# ProPrj_51__2025-11-10-23-27-29.net
KiCad netlist of a schematic drawn in EasyEDA Pro
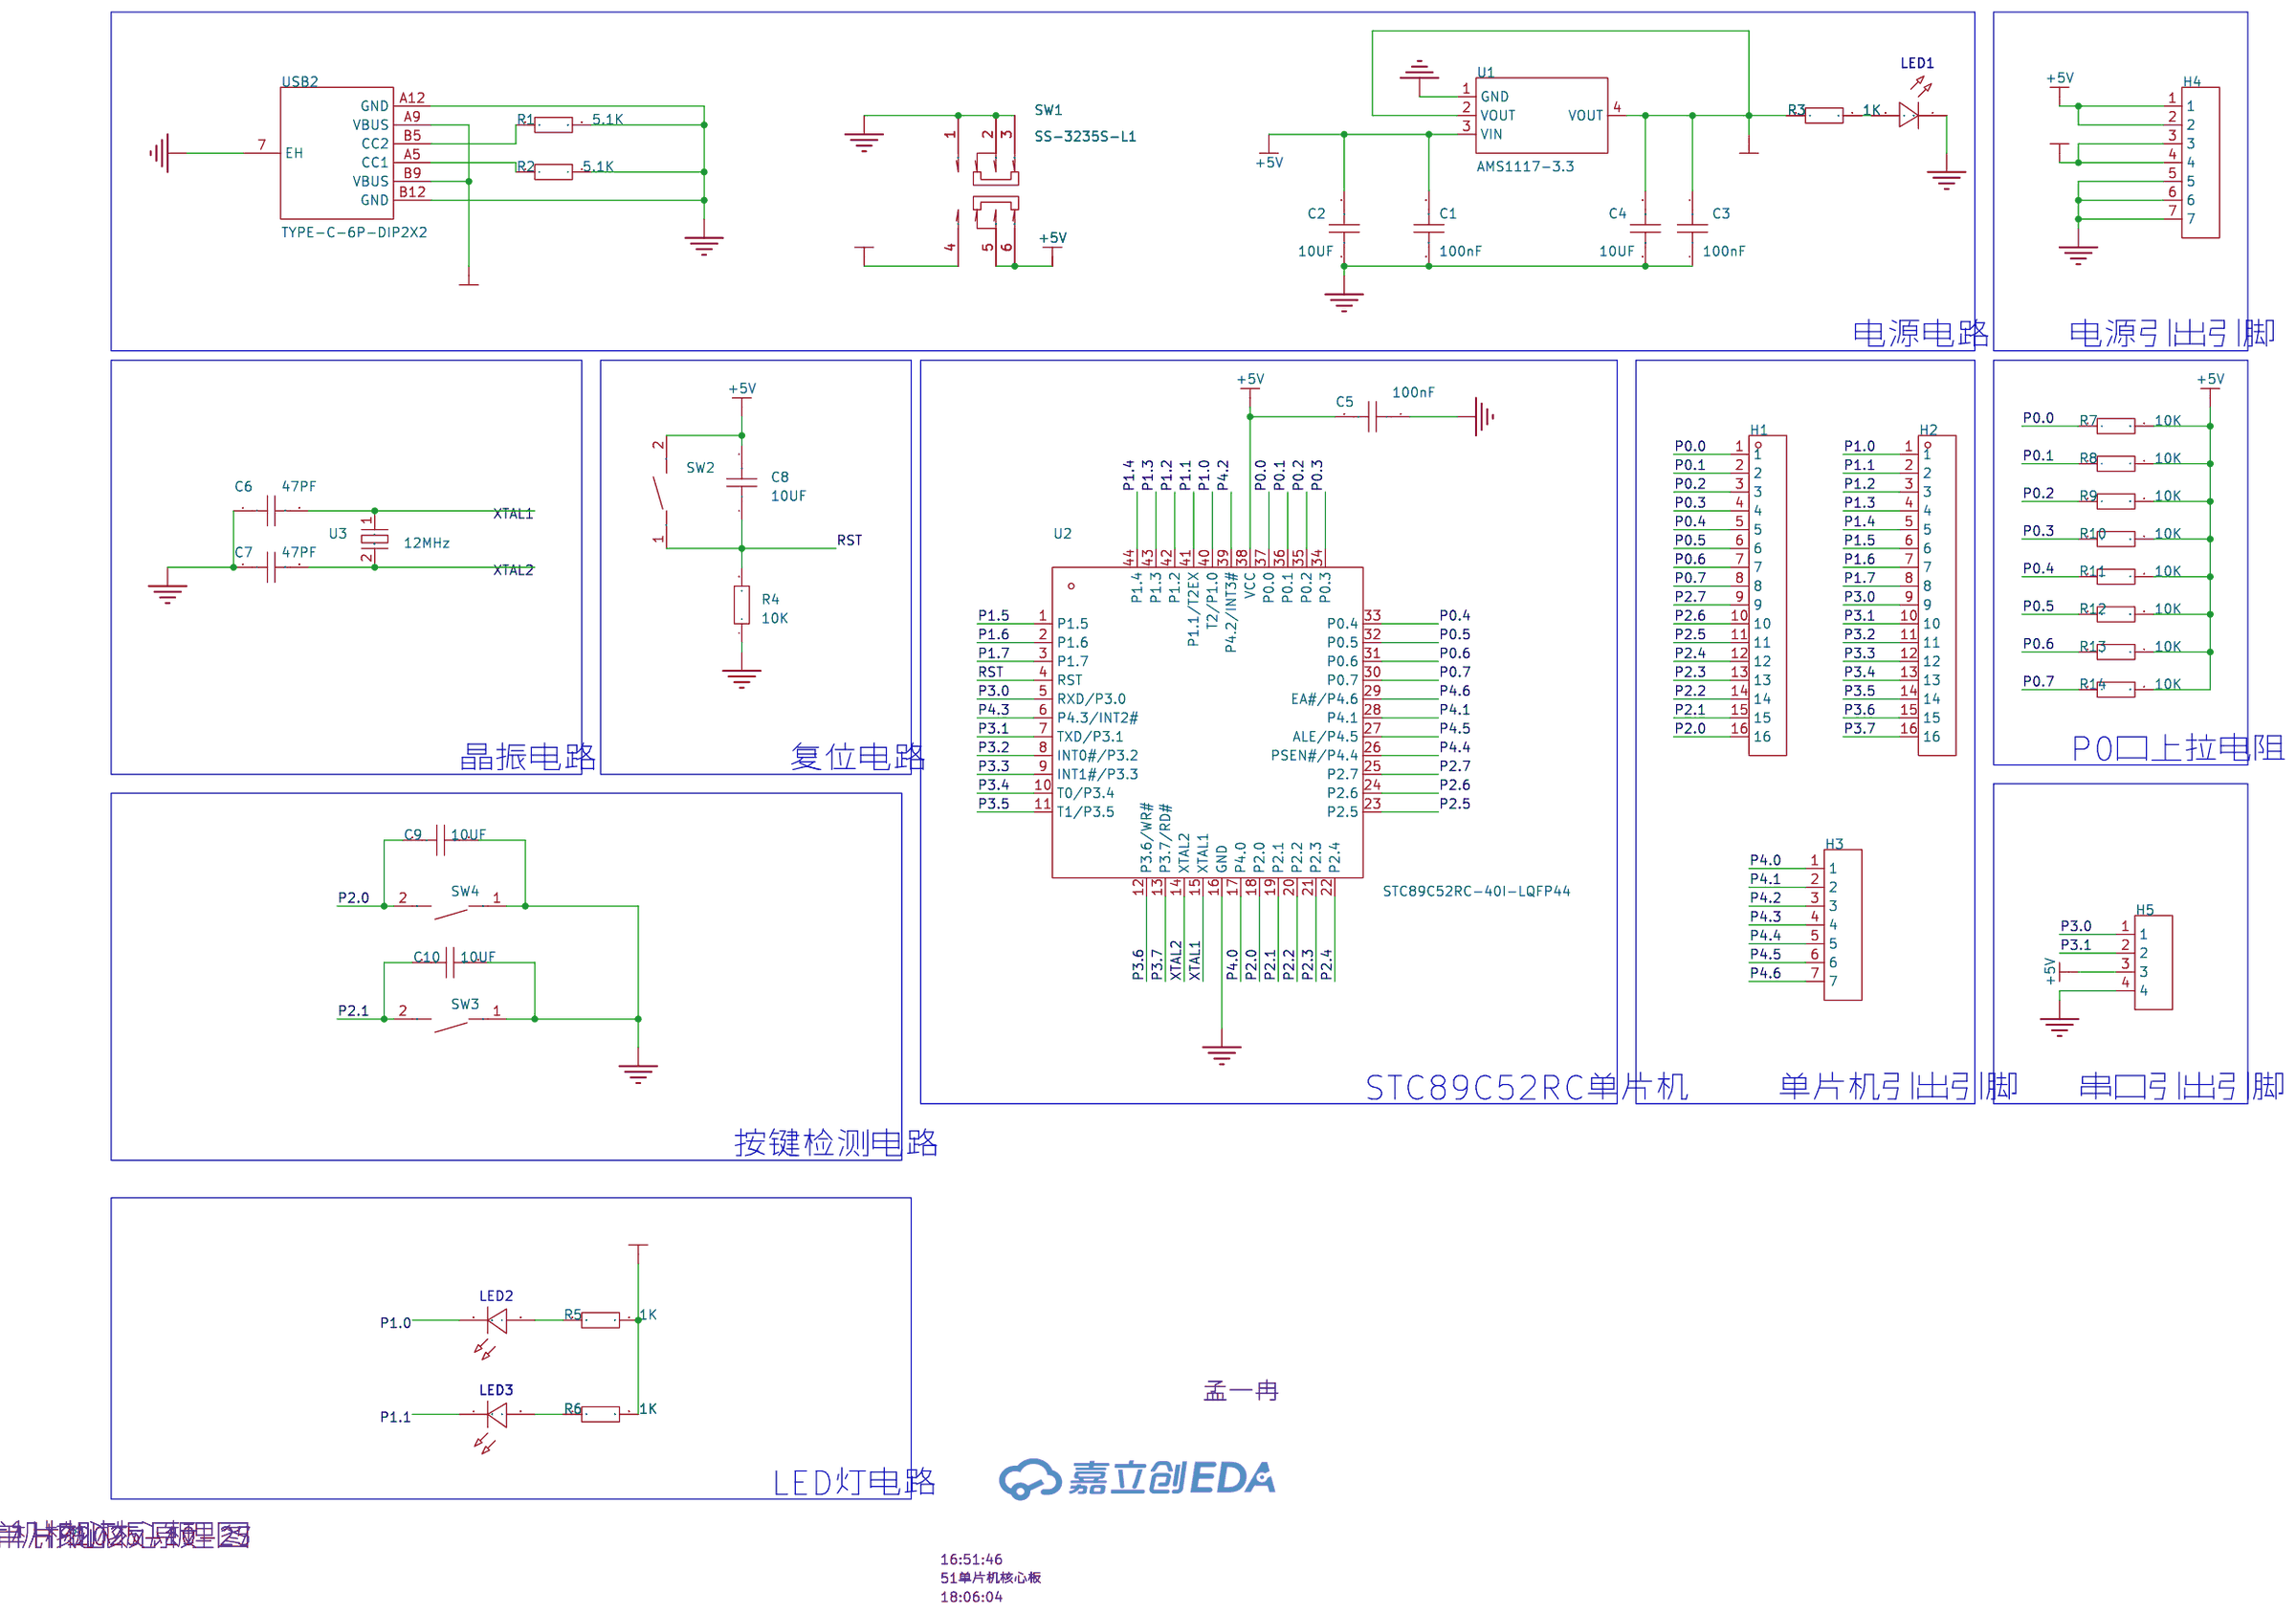
[diagram p0: schematic sheet]

(export (version "E")
  (design (tool "Eeschema 10.0.6"))
  (components
    (comp (ref "C1")
      (value "100nF")
      (footprint "easyedapro:C0805")
      (libsource (lib "easyedapro") (part "Capacitance"))
    )
    (comp (ref "C2")
      (value "10UF")
      (footprint "easyedapro:C0805")
      (libsource (lib "easyedapro") (part "Capacitance"))
    )
    (comp (ref "C3")
      (value "100nF")
      (footprint "easyedapro:C0805")
      (libsource (lib "easyedapro") (part "Capacitance"))
    )
    (comp (ref "C4")
      (value "10UF")
      (footprint "easyedapro:C0805")
      (libsource (lib "easyedapro") (part "Capacitance"))
    )
    (comp (ref "C5")
      (value "100nF")
      (footprint "easyedapro:C0805")
      (libsource (lib "easyedapro") (part "Capacitance"))
    )
    (comp (ref "C6")
      (value "47PF")
      (footprint "easyedapro:C0805")
      (libsource (lib "easyedapro") (part "Capacitance"))
    )
    (comp (ref "C7")
      (value "47PF")
      (footprint "easyedapro:C0805")
      (libsource (lib "easyedapro") (part "Capacitance"))
    )
    (comp (ref "C8")
      (value "10UF")
      (footprint "easyedapro:C0805")
      (libsource (lib "easyedapro") (part "Capacitance"))
    )
    (comp (ref "C9")
      (value "10UF")
      (footprint "easyedapro:C0805")
      (libsource (lib "easyedapro") (part "Capacitance"))
    )
    (comp (ref "C10")
      (value "10UF")
      (footprint "easyedapro:C0805")
      (libsource (lib "easyedapro") (part "Capacitance"))
    )
    (comp (ref "H1")
      (value "~")
      (footprint "easyedapro:HDR-TH_16P-P2.54-V-M")
      (libsource (lib "easyedapro") (part "HDR_2.54-1x16P"))
    )
    (comp (ref "H2")
      (value "~")
      (footprint "easyedapro:HDR-TH_16P-P2.54-V-M")
      (libsource (lib "easyedapro") (part "HDR_2.54-1x16P"))
    )
    (comp (ref "H3")
      (value "~")
      (footprint "easyedapro:HDR-TH_7P-P2.54-V-M")
      (libsource (lib "easyedapro") (part "PZ254V-11-07P"))
    )
    (comp (ref "H4")
      (value "~")
      (footprint "easyedapro:HDR-TH_7P-P2.54-V-M")
      (libsource (lib "easyedapro") (part "PZ254V-11-07P"))
    )
    (comp (ref "H5")
      (value "~")
      (footprint "easyedapro:HDR-TH_4P-P2.54-V-M")
      (libsource (lib "easyedapro") (part "PZ254V-11-04P"))
    )
    (comp (ref "LED1")
      (value "~")
      (footprint "easyedapro:LED_0805")
      (libsource (lib "easyedapro") (part "LED_G"))
    )
    (comp (ref "LED2")
      (value "~")
      (footprint "easyedapro:LED_0805")
      (libsource (lib "easyedapro") (part "LED_G"))
    )
    (comp (ref "LED3")
      (value "~")
      (footprint "easyedapro:LED_0805")
      (libsource (lib "easyedapro") (part "LED_G"))
    )
    (comp (ref "R1") (value "5.1K") (footprint "easyedapro:R0805") (libsource (lib "easyedapro") (part "电阻")))
    (comp (ref "R2") (value "5.1K") (footprint "easyedapro:R0805") (libsource (lib "easyedapro") (part "电阻")))
    (comp (ref "R3") (value "1K") (footprint "easyedapro:R0805") (libsource (lib "easyedapro") (part "电阻")))
    (comp (ref "R4") (value "10K") (footprint "easyedapro:R0805") (libsource (lib "easyedapro") (part "电阻")))
    (comp (ref "R5") (value "1K") (footprint "easyedapro:R0805") (libsource (lib "easyedapro") (part "电阻")))
    (comp (ref "R6") (value "1K") (footprint "easyedapro:R0805") (libsource (lib "easyedapro") (part "电阻")))
    (comp (ref "R7") (value "10K") (footprint "easyedapro:R0805") (libsource (lib "easyedapro") (part "电阻")))
    (comp (ref "R8") (value "10K") (footprint "easyedapro:R0805") (libsource (lib "easyedapro") (part "电阻")))
    (comp (ref "R9") (value "10K") (footprint "easyedapro:R0805") (libsource (lib "easyedapro") (part "电阻")))
    (comp (ref "R10") (value "10K") (footprint "easyedapro:R0805") (libsource (lib "easyedapro") (part "电阻")))
    (comp (ref "R11") (value "10K") (footprint "easyedapro:R0805") (libsource (lib "easyedapro") (part "电阻")))
    (comp (ref "R12") (value "10K") (footprint "easyedapro:R0805") (libsource (lib "easyedapro") (part "电阻")))
    (comp (ref "R13") (value "10K") (footprint "easyedapro:R0805") (libsource (lib "easyedapro") (part "电阻")))
    (comp (ref "R14") (value "10K") (footprint "easyedapro:R0805") (libsource (lib "easyedapro") (part "电阻")))
    (comp (ref "SW1")
      (value "SS-3235S-L1")
      (footprint "easyedapro:SW-SMD_SS-3235S-LX")
      (description "电路结构:双刀双掷;安装方式:卧贴;开关颜色:黑色;额定电流:50mA;额定电压:12V;工作寿命:1万次;")
      (fields (field (name "Manufacturer") "XKB Connection(中国星坤)"))
      (libsource (lib "easyedapro") (part "SS-3235S-L1"))
    )
    (comp (ref "SW2")
      (value "轻触按键3*4*H")
      (footprint "easyedapro:SW-SMD_L4.0-W2.9-LS5.0")
      (libsource (lib "easyedapro") (part "轻触按键3*4*H"))
    )
    (comp (ref "SW3")
      (value "轻触按键3*4*H")
      (footprint "easyedapro:SW-SMD_L4.0-W2.9-LS5.0")
      (libsource (lib "easyedapro") (part "轻触按键3*4*H"))
    )
    (comp (ref "SW4")
      (value "轻触按键3*4*H")
      (footprint "easyedapro:SW-SMD_L4.0-W2.9-LS5.0")
      (libsource (lib "easyedapro") (part "轻触按键3*4*H"))
    )
    (comp (ref "U1")
      (value "AMS1117-3.3")
      (footprint "easyedapro:SOT-223-3_L6.5-W3.4-P2.30-LS7.0-BR")
      (description "输出类型:固定;工作电压:16V;输出电压:3.3V;输出电流:1A;电源纹波抑制比(PSRR):72dB@(120Hz);输出极性:正极;")
      (fields (field (name "Manufacturer") "AMS"))
      (libsource (lib "easyedapro") (part "AMS1117-3.3"))
    )
    (comp (ref "U2")
      (value "STC89C52RC-40I-LQFP44")
      (footprint "easyedapro:LQFP-44_L10.0-W10.0-P0.80-LS12.0-BL")
      (description "CPU内核:51系列;应用领域:-;")
      (fields (field (name "Manufacturer") "STC"))
      (libsource (lib "easyedapro") (part "STC89C52RC-40I_C8707"))
    )
    (comp (ref "U3")
      (value "12MHz")
      (footprint "easyedapro:CRYSTAL-SMD_L11.4-W4.7-LS12.7")
      (description "频率:12MHz;常温频差:±30ppm;外接负载电容:18pF;频率稳定度(全温):±35ppm;")
      (fields
        (field (name "Manufacturer Part") "ABLS-12.000MHZ-B4H-T")
        (field (name "Manufacturer") "ABRACON")
      )
      (libsource (lib "easyedapro") (part "ABLS-12.000MHZ-B4H-T"))
    )
    (comp (ref "USB2")
      (value "TYPE-C-6P-DIP2X2")
      (footprint "easyedapro:TYPE-C-SMD_TYPE-C-6P")
      (libsource (lib "easyedapro") (part "TYPE-C-6P-DIP2X2"))
    )
  )
  (nets
    (net (code "1") (name "+3.3V") (class "Default")
      (node (ref "C3") (pin "2") (pinfunction "2_2") (pintype "input"))
      (node (ref "C4") (pin "2") (pinfunction "2_2") (pintype "input"))
      (node (ref "H4") (pin "3") (pinfunction "3_3") (pintype "unspecified"))
      (node (ref "H4") (pin "4") (pinfunction "4_4") (pintype "unspecified"))
      (node (ref "R3") (pin "1") (pinfunction "1_1") (pintype "input"))
      (node (ref "R5") (pin "2") (pinfunction "2_2") (pintype "input"))
      (node (ref "R6") (pin "2") (pinfunction "2_2") (pintype "input"))
      (node (ref "U1") (pin "2") (pinfunction "VOUT_2") (pintype "unspecified"))
      (node (ref "U1") (pin "4") (pinfunction "VOUT_4") (pintype "unspecified"))
    )
    (net (code "2") (name "+5V") (class "Default")
      (node (ref "C1") (pin "2") (pinfunction "2_2") (pintype "input"))
      (node (ref "C2") (pin "2") (pinfunction "2_2") (pintype "input"))
      (node (ref "C5") (pin "2") (pinfunction "2_2") (pintype "input"))
      (node (ref "C8") (pin "2") (pinfunction "2_2") (pintype "input"))
      (node (ref "H4") (pin "1") (pinfunction "1_1") (pintype "unspecified"))
      (node (ref "H4") (pin "2") (pinfunction "2_2") (pintype "unspecified"))
      (node (ref "H5") (pin "3") (pinfunction "3_3") (pintype "unspecified"))
      (node (ref "R10") (pin "2") (pinfunction "2_2") (pintype "input"))
      (node (ref "R11") (pin "2") (pinfunction "2_2") (pintype "input"))
      (node (ref "R12") (pin "2") (pinfunction "2_2") (pintype "input"))
      (node (ref "R13") (pin "2") (pinfunction "2_2") (pintype "input"))
      (node (ref "R14") (pin "2") (pinfunction "2_2") (pintype "input"))
      (node (ref "R7") (pin "2") (pinfunction "2_2") (pintype "input"))
      (node (ref "R8") (pin "2") (pinfunction "2_2") (pintype "input"))
      (node (ref "R9") (pin "2") (pinfunction "2_2") (pintype "input"))
      (node (ref "SW1") (pin "5") (pinfunction "5_5") (pintype "unspecified"))
      (node (ref "SW1") (pin "6") (pinfunction "6_6") (pintype "unspecified"))
      (node (ref "SW2") (pin "2") (pinfunction "2_2") (pintype "unspecified"))
      (node (ref "U1") (pin "3") (pinfunction "VIN_3") (pintype "unspecified"))
      (node (ref "U2") (pin "38") (pinfunction "VCC_38") (pintype "unspecified"))
    )
    (net (code "3") (name "/P0.0") (class "Default")
      (node (ref "H1") (pin "1") (pinfunction "1_1") (pintype "input"))
      (node (ref "R7") (pin "1") (pinfunction "1_1") (pintype "input"))
      (node (ref "U2") (pin "37") (pinfunction "P0.0_37") (pintype "unspecified"))
    )
    (net (code "4") (name "/P0.1") (class "Default")
      (node (ref "H1") (pin "2") (pinfunction "2_2") (pintype "input"))
      (node (ref "R8") (pin "1") (pinfunction "1_1") (pintype "input"))
      (node (ref "U2") (pin "36") (pinfunction "P0.1_36") (pintype "unspecified"))
    )
    (net (code "5") (name "/P0.2") (class "Default")
      (node (ref "H1") (pin "3") (pinfunction "3_3") (pintype "input"))
      (node (ref "R9") (pin "1") (pinfunction "1_1") (pintype "input"))
      (node (ref "U2") (pin "35") (pinfunction "P0.2_35") (pintype "unspecified"))
    )
    (net (code "6") (name "/P0.3") (class "Default")
      (node (ref "H1") (pin "4") (pinfunction "4_4") (pintype "input"))
      (node (ref "R10") (pin "1") (pinfunction "1_1") (pintype "input"))
      (node (ref "U2") (pin "34") (pinfunction "P0.3_34") (pintype "unspecified"))
    )
    (net (code "7") (name "/P0.4") (class "Default")
      (node (ref "H1") (pin "5") (pinfunction "5_5") (pintype "input"))
      (node (ref "R11") (pin "1") (pinfunction "1_1") (pintype "input"))
      (node (ref "U2") (pin "33") (pinfunction "P0.4_33") (pintype "unspecified"))
    )
    (net (code "8") (name "/P0.5") (class "Default")
      (node (ref "H1") (pin "6") (pinfunction "6_6") (pintype "input"))
      (node (ref "R12") (pin "1") (pinfunction "1_1") (pintype "input"))
      (node (ref "U2") (pin "32") (pinfunction "P0.5_32") (pintype "unspecified"))
    )
    (net (code "9") (name "/P0.6") (class "Default")
      (node (ref "H1") (pin "7") (pinfunction "7_7") (pintype "input"))
      (node (ref "R13") (pin "1") (pinfunction "1_1") (pintype "input"))
      (node (ref "U2") (pin "31") (pinfunction "P0.6_31") (pintype "unspecified"))
    )
    (net (code "10") (name "/P0.7") (class "Default")
      (node (ref "H1") (pin "8") (pinfunction "8_8") (pintype "input"))
      (node (ref "R14") (pin "1") (pinfunction "1_1") (pintype "input"))
      (node (ref "U2") (pin "30") (pinfunction "P0.7_30") (pintype "unspecified"))
    )
    (net (code "11") (name "/P1.0") (class "Default")
      (node (ref "H2") (pin "1") (pinfunction "1_1") (pintype "input"))
      (node (ref "LED2") (pin "1") (pinfunction "C_1") (pintype "input"))
      (node (ref "U2") (pin "40") (pinfunction "T2/P1.0_40") (pintype "unspecified"))
    )
    (net (code "12") (name "/P1.1") (class "Default")
      (node (ref "H2") (pin "2") (pinfunction "2_2") (pintype "input"))
      (node (ref "LED3") (pin "1") (pinfunction "C_1") (pintype "input"))
      (node (ref "U2") (pin "41") (pinfunction "P1.1/T2EX_41") (pintype "unspecified"))
    )
    (net (code "13") (name "/P1.2") (class "Default")
      (node (ref "H2") (pin "3") (pinfunction "3_3") (pintype "input"))
      (node (ref "U2") (pin "42") (pinfunction "P1.2_42") (pintype "unspecified"))
    )
    (net (code "14") (name "/P1.3") (class "Default")
      (node (ref "H2") (pin "4") (pinfunction "4_4") (pintype "input"))
      (node (ref "U2") (pin "43") (pinfunction "P1.3_43") (pintype "unspecified"))
    )
    (net (code "15") (name "/P1.4") (class "Default")
      (node (ref "H2") (pin "5") (pinfunction "5_5") (pintype "input"))
      (node (ref "U2") (pin "44") (pinfunction "P1.4_44") (pintype "unspecified"))
    )
    (net (code "16") (name "/P1.5") (class "Default")
      (node (ref "H2") (pin "6") (pinfunction "6_6") (pintype "input"))
      (node (ref "U2") (pin "1") (pinfunction "P1.5_1") (pintype "unspecified"))
    )
    (net (code "17") (name "/P1.6") (class "Default")
      (node (ref "H2") (pin "7") (pinfunction "7_7") (pintype "input"))
      (node (ref "U2") (pin "2") (pinfunction "P1.6_2") (pintype "unspecified"))
    )
    (net (code "18") (name "/P1.7") (class "Default")
      (node (ref "H2") (pin "8") (pinfunction "8_8") (pintype "input"))
      (node (ref "U2") (pin "3") (pinfunction "P1.7_3") (pintype "unspecified"))
    )
    (net (code "19") (name "/P2.0") (class "Default")
      (node (ref "C9") (pin "1") (pinfunction "1_1") (pintype "input"))
      (node (ref "H1") (pin "16") (pinfunction "16_16") (pintype "input"))
      (node (ref "SW4") (pin "2") (pinfunction "2_2") (pintype "unspecified"))
      (node (ref "U2") (pin "18") (pinfunction "P2.0_18") (pintype "unspecified"))
    )
    (net (code "20") (name "/P2.1") (class "Default")
      (node (ref "C10") (pin "1") (pinfunction "1_1") (pintype "input"))
      (node (ref "H1") (pin "15") (pinfunction "15_15") (pintype "input"))
      (node (ref "SW3") (pin "2") (pinfunction "2_2") (pintype "unspecified"))
      (node (ref "U2") (pin "19") (pinfunction "P2.1_19") (pintype "unspecified"))
    )
    (net (code "21") (name "/P2.2") (class "Default")
      (node (ref "H1") (pin "14") (pinfunction "14_14") (pintype "input"))
      (node (ref "U2") (pin "20") (pinfunction "P2.2_20") (pintype "unspecified"))
    )
    (net (code "22") (name "/P2.3") (class "Default")
      (node (ref "H1") (pin "13") (pinfunction "13_13") (pintype "input"))
      (node (ref "U2") (pin "21") (pinfunction "P2.3_21") (pintype "unspecified"))
    )
    (net (code "23") (name "/P2.4") (class "Default")
      (node (ref "H1") (pin "12") (pinfunction "12_12") (pintype "input"))
      (node (ref "U2") (pin "22") (pinfunction "P2.4_22") (pintype "unspecified"))
    )
    (net (code "24") (name "/P2.5") (class "Default")
      (node (ref "H1") (pin "11") (pinfunction "11_11") (pintype "input"))
      (node (ref "U2") (pin "23") (pinfunction "P2.5_23") (pintype "unspecified"))
    )
    (net (code "25") (name "/P2.6") (class "Default")
      (node (ref "H1") (pin "10") (pinfunction "10_10") (pintype "input"))
      (node (ref "U2") (pin "24") (pinfunction "P2.6_24") (pintype "unspecified"))
    )
    (net (code "26") (name "/P2.7") (class "Default")
      (node (ref "H1") (pin "9") (pinfunction "9_9") (pintype "input"))
      (node (ref "U2") (pin "25") (pinfunction "P2.7_25") (pintype "unspecified"))
    )
    (net (code "27") (name "/P3.0") (class "Default")
      (node (ref "H2") (pin "9") (pinfunction "9_9") (pintype "input"))
      (node (ref "H5") (pin "1") (pinfunction "1_1") (pintype "unspecified"))
      (node (ref "U2") (pin "5") (pinfunction "RXD/P3.0_5") (pintype "unspecified"))
    )
    (net (code "28") (name "/P3.1") (class "Default")
      (node (ref "H2") (pin "10") (pinfunction "10_10") (pintype "input"))
      (node (ref "H5") (pin "2") (pinfunction "2_2") (pintype "unspecified"))
      (node (ref "U2") (pin "7") (pinfunction "TXD/P3.1_7") (pintype "unspecified"))
    )
    (net (code "29") (name "/P3.2") (class "Default")
      (node (ref "H2") (pin "11") (pinfunction "11_11") (pintype "input"))
      (node (ref "U2") (pin "8") (pinfunction "INT0#/P3.2_8") (pintype "unspecified"))
    )
    (net (code "30") (name "/P3.3") (class "Default")
      (node (ref "H2") (pin "12") (pinfunction "12_12") (pintype "input"))
      (node (ref "U2") (pin "9") (pinfunction "INT1#/P3.3_9") (pintype "unspecified"))
    )
    (net (code "31") (name "/P3.4") (class "Default")
      (node (ref "H2") (pin "13") (pinfunction "13_13") (pintype "input"))
      (node (ref "U2") (pin "10") (pinfunction "T0/P3.4_10") (pintype "unspecified"))
    )
    (net (code "32") (name "/P3.5") (class "Default")
      (node (ref "H2") (pin "14") (pinfunction "14_14") (pintype "input"))
      (node (ref "U2") (pin "11") (pinfunction "T1/P3.5_11") (pintype "unspecified"))
    )
    (net (code "33") (name "/P3.6") (class "Default")
      (node (ref "H2") (pin "15") (pinfunction "15_15") (pintype "input"))
      (node (ref "U2") (pin "12") (pinfunction "P3.6/WR#_12") (pintype "unspecified"))
    )
    (net (code "34") (name "/P3.7") (class "Default")
      (node (ref "H2") (pin "16") (pinfunction "16_16") (pintype "input"))
      (node (ref "U2") (pin "13") (pinfunction "P3.7/RD#_13") (pintype "unspecified"))
    )
    (net (code "35") (name "/P4.0") (class "Default")
      (node (ref "H3") (pin "1") (pinfunction "1_1") (pintype "unspecified"))
      (node (ref "U2") (pin "17") (pinfunction "P4.0_17") (pintype "unspecified"))
    )
    (net (code "36") (name "/P4.1") (class "Default")
      (node (ref "H3") (pin "2") (pinfunction "2_2") (pintype "unspecified"))
      (node (ref "U2") (pin "28") (pinfunction "P4.1_28") (pintype "unspecified"))
    )
    (net (code "37") (name "/P4.2") (class "Default")
      (node (ref "H3") (pin "3") (pinfunction "3_3") (pintype "unspecified"))
      (node (ref "U2") (pin "39") (pinfunction "P4.2/INT3#_39") (pintype "unspecified"))
    )
    (net (code "38") (name "/P4.3") (class "Default")
      (node (ref "H3") (pin "4") (pinfunction "4_4") (pintype "unspecified"))
      (node (ref "U2") (pin "6") (pinfunction "P4.3/INT2#_6") (pintype "unspecified"))
    )
    (net (code "39") (name "/P4.4") (class "Default")
      (node (ref "H3") (pin "5") (pinfunction "5_5") (pintype "unspecified"))
      (node (ref "U2") (pin "26") (pinfunction "PSEN#/P4.4_26") (pintype "unspecified"))
    )
    (net (code "40") (name "/P4.5") (class "Default")
      (node (ref "H3") (pin "6") (pinfunction "6_6") (pintype "unspecified"))
      (node (ref "U2") (pin "27") (pinfunction "ALE/P4.5_27") (pintype "unspecified"))
    )
    (net (code "41") (name "/P4.6") (class "Default")
      (node (ref "H3") (pin "7") (pinfunction "7_7") (pintype "unspecified"))
      (node (ref "U2") (pin "29") (pinfunction "EA#/P4.6_29") (pintype "unspecified"))
    )
    (net (code "42") (name "/RST") (class "Default")
      (node (ref "C8") (pin "1") (pinfunction "1_1") (pintype "input"))
      (node (ref "R4") (pin "2") (pinfunction "2_2") (pintype "input"))
      (node (ref "SW2") (pin "1") (pinfunction "1_1") (pintype "unspecified"))
      (node (ref "U2") (pin "4") (pinfunction "RST_4") (pintype "unspecified"))
    )
    (net (code "43") (name "/XTAL1") (class "Default")
      (node (ref "C6") (pin "2") (pinfunction "2_2") (pintype "input"))
      (node (ref "U2") (pin "15") (pinfunction "XTAL1_15") (pintype "unspecified"))
      (node (ref "U3") (pin "1") (pinfunction "1_1") (pintype "input"))
    )
    (net (code "44") (name "/XTAL2") (class "Default")
      (node (ref "C7") (pin "2") (pinfunction "2_2") (pintype "input"))
      (node (ref "U2") (pin "14") (pinfunction "XTAL2_14") (pintype "unspecified"))
      (node (ref "U3") (pin "2") (pinfunction "GND_2") (pintype "input"))
    )
    (net (code "45") (name "GND") (class "Default")
      (node (ref "C1") (pin "1") (pinfunction "1_1") (pintype "input"))
      (node (ref "C10") (pin "2") (pinfunction "2_2") (pintype "input"))
      (node (ref "C2") (pin "1") (pinfunction "1_1") (pintype "input"))
      (node (ref "C3") (pin "1") (pinfunction "1_1") (pintype "input"))
      (node (ref "C4") (pin "1") (pinfunction "1_1") (pintype "input"))
      (node (ref "C5") (pin "1") (pinfunction "1_1") (pintype "input"))
      (node (ref "C6") (pin "1") (pinfunction "1_1") (pintype "input"))
      (node (ref "C7") (pin "1") (pinfunction "1_1") (pintype "input"))
      (node (ref "C9") (pin "2") (pinfunction "2_2") (pintype "input"))
      (node (ref "H4") (pin "5") (pinfunction "5_5") (pintype "unspecified"))
      (node (ref "H4") (pin "6") (pinfunction "6_6") (pintype "unspecified"))
      (node (ref "H4") (pin "7") (pinfunction "7_7") (pintype "unspecified"))
      (node (ref "H5") (pin "4") (pinfunction "4_4") (pintype "unspecified"))
      (node (ref "LED1") (pin "1") (pinfunction "C_1") (pintype "input"))
      (node (ref "R1") (pin "2") (pinfunction "2_2") (pintype "input"))
      (node (ref "R2") (pin "2") (pinfunction "2_2") (pintype "input"))
      (node (ref "R4") (pin "1") (pinfunction "1_1") (pintype "input"))
      (node (ref "SW1") (pin "1") (pinfunction "1_1") (pintype "unspecified"))
      (node (ref "SW1") (pin "2") (pinfunction "2_2") (pintype "unspecified"))
      (node (ref "SW1") (pin "3") (pinfunction "3_3") (pintype "unspecified"))
      (node (ref "SW3") (pin "1") (pinfunction "1_1") (pintype "unspecified"))
      (node (ref "SW4") (pin "1") (pinfunction "1_1") (pintype "unspecified"))
      (node (ref "U1") (pin "1") (pinfunction "GND_1") (pintype "unspecified"))
      (node (ref "U2") (pin "16") (pinfunction "GND_16") (pintype "unspecified"))
      (node (ref "USB2") (pin "7") (pinfunction "EH_7") (pintype "unspecified"))
      (node (ref "USB2") (pin "A12") (pinfunction "GND_A12") (pintype "unspecified"))
      (node (ref "USB2") (pin "B12") (pinfunction "GND_B12") (pintype "unspecified"))
    )
    (net (code "46") (name "Net-(LED1-A)") (class "Default")
      (node (ref "LED1") (pin "2") (pinfunction "A_2") (pintype "input"))
      (node (ref "R3") (pin "2") (pinfunction "2_2") (pintype "input"))
    )
    (net (code "47") (name "Net-(LED2-A)") (class "Default")
      (node (ref "LED2") (pin "2") (pinfunction "A_2") (pintype "input"))
      (node (ref "R5") (pin "1") (pinfunction "1_1") (pintype "input"))
    )
    (net (code "48") (name "Net-(LED3-A)") (class "Default")
      (node (ref "LED3") (pin "2") (pinfunction "A_2") (pintype "input"))
      (node (ref "R6") (pin "1") (pinfunction "1_1") (pintype "input"))
    )
    (net (code "49") (name "Net-(USB2-CC1)") (class "Default")
      (node (ref "R2") (pin "1") (pinfunction "1_1") (pintype "input"))
      (node (ref "USB2") (pin "A5") (pinfunction "CC1_A5") (pintype "unspecified"))
    )
    (net (code "50") (name "Net-(USB2-CC2)") (class "Default")
      (node (ref "R1") (pin "1") (pinfunction "1_1") (pintype "input"))
      (node (ref "USB2") (pin "B5") (pinfunction "CC2_B5") (pintype "unspecified"))
    )
    (net (code "51") (name "VCC+5V") (class "Default")
      (node (ref "SW1") (pin "4") (pinfunction "4_4") (pintype "unspecified"))
      (node (ref "USB2") (pin "A9") (pinfunction "VBUS_A9") (pintype "unspecified"))
      (node (ref "USB2") (pin "B9") (pinfunction "VBUS_B9") (pintype "unspecified"))
    )
  )
)
